# GSM_Power_LED_Driver.net
KiCad netlist of a schematic drawn in Altium Designer
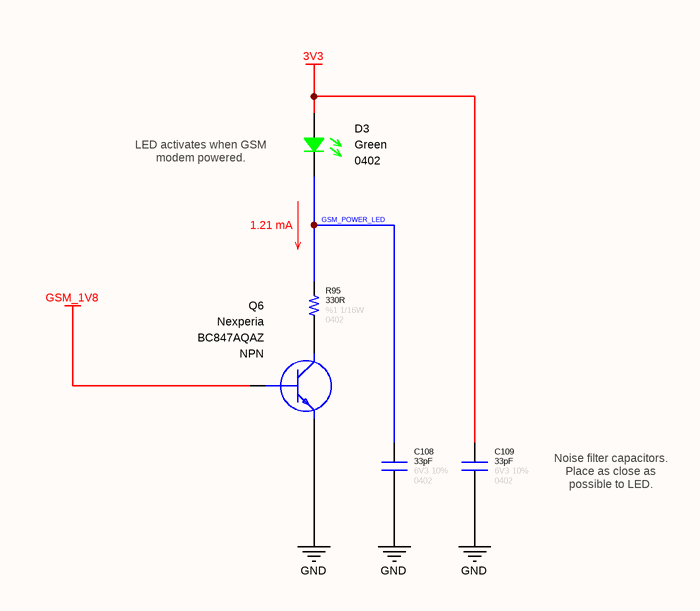
[diagram p0: GSM Power LED Driver.SchDoc]

(export (version "E")
  (design (tool "Eeschema 10.0.6"))
  (components
    (comp (ref "C108")
      (value "33pF")
      (footprint "CAPACITOR_0402")
      (description "Capacitor - 33pF [0402] (Ceramic)")
      (fields
        (field (name "MANUFACTURER PART NUMBER") "C0402C330J9RACAUTO")
        (field (name "TOLERANCE") "10%")
        (field (name "CASE") "0402")
        (field (name "VOLTAGE") "6V3")
      )
      (libsource (lib "Akkoyun") (part "Capacitor - 33pF [0402-6V3]"))
    )
    (comp (ref "C109")
      (value "33pF")
      (footprint "CAPACITOR_0402")
      (description "Capacitor - 33pF [0402] (Ceramic)")
      (fields
        (field (name "MANUFACTURER PART NUMBER") "C0402C330J9RACAUTO")
        (field (name "TOLERANCE") "10%")
        (field (name "CASE") "0402")
        (field (name "VOLTAGE") "6V3")
      )
      (libsource (lib "Akkoyun") (part "Capacitor - 33pF [0402-6V3]"))
    )
    (comp (ref "D3")
      (value "SMD LED (Green)")
      (footprint "LED_0402")
      (description "Standard LEDs - SMD MINI-MOLD ULTRA COMPACT GREEN")
      (fields
        (field (name "MANUFACTURER PART NUMBER") "SML-P12MTT86R")
        (field (name "CASE") "0402")
        (field (name "COLOR") "Green")
      )
      (libsource (lib "Akkoyun") (part "Diode - LED (0402-Green)"))
    )
    (comp (ref "Q6")
      (value "BC847AQAZ")
      (footprint "SOT1215")
      (description "Bipolar NPN Transistors")
      (fields
        (field (name "MANUFACTURER NAME") "Nexperia")
        (field (name "MANUFACTURER PART NUMBER") "BC847AQAZ")
        (field (name "POLARITY") "NPN")
      )
      (libsource (lib "Akkoyun") (part "Transistor - BC847"))
    )
    (comp (ref "R95")
      (value "330R")
      (footprint "RESISTOR_0402")
      (description "Thick Film Resistors - SMD 1/16 W 330 Ohm 1%")
      (fields
        (field (name "MANUFACTURER PART NUMBER") "CRCW0402330RFKED")
        (field (name "CASE") "0402")
        (field (name "TOLERANCE") "%1")
        (field (name "POWER") "1/16W")
        (field (name "Comment") "330R - 0402 - %1 - 1/16W")
      )
      (libsource (lib "Akkoyun") (part "Resistor - 330R [0402]"))
    )
  )
  (nets
    (net (code "1") (name "/GSM_POWER_LED") (class "Default")
      (node (ref "C108") (pin "2") (pinfunction "2_2") (pintype "passive"))
      (node (ref "D3") (pin "1") (pinfunction "1_1") (pintype "passive"))
      (node (ref "R95") (pin "2") (pinfunction "2_2") (pintype "passive"))
    )
    (net (code "2") (name "3V3") (class "Default")
      (node (ref "C109") (pin "2") (pinfunction "2_2") (pintype "passive"))
      (node (ref "D3") (pin "2") (pinfunction "2_2") (pintype "passive"))
    )
    (net (code "3") (name "GND") (class "Default")
      (node (ref "C108") (pin "1") (pinfunction "1_1") (pintype "passive"))
      (node (ref "C109") (pin "1") (pinfunction "1_1") (pintype "passive"))
      (node (ref "Q6") (pin "2") (pinfunction "E_2") (pintype "passive"))
    )
    (net (code "4") (name "GSM_1V8") (class "Default")
      (node (ref "Q6") (pin "1") (pinfunction "B_1") (pintype "passive"))
    )
    (net (code "5") (name "Net-(Q6-C)") (class "Default")
      (node (ref "Q6") (pin "3") (pinfunction "C_3") (pintype "passive"))
      (node (ref "R95") (pin "1") (pinfunction "1_1") (pintype "passive"))
    )
  )
)
